# CROSS.net
KiCad netlist of a schematic drawn in EAGLE
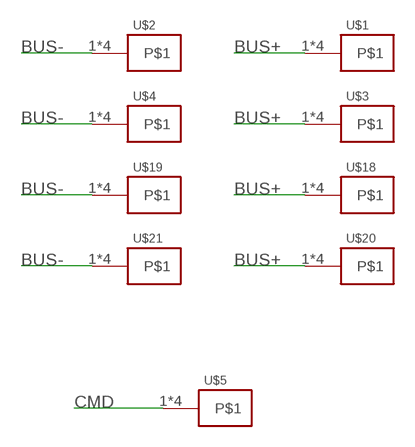
[diagram p0: schematic, sheet 1]

(export (version "E")
  (design (tool "Eeschema 10.0.6"))
  (components
    (comp (ref "U$1")
      (value "KCONNECT-")
      (footprint "eagle-import:KCONNECT-")
      (libsource (lib "eagle-import") (part "KCONNECT-"))
    )
    (comp (ref "U$2")
      (value "KCONNECT-")
      (footprint "eagle-import:KCONNECT-")
      (libsource (lib "eagle-import") (part "KCONNECT-"))
    )
    (comp (ref "U$3")
      (value "KCONNECT-")
      (footprint "eagle-import:KCONNECT-")
      (libsource (lib "eagle-import") (part "KCONNECT-"))
    )
    (comp (ref "U$4")
      (value "KCONNECT-")
      (footprint "eagle-import:KCONNECT-")
      (libsource (lib "eagle-import") (part "KCONNECT-"))
    )
    (comp (ref "U$5")
      (value "KCONNECTQUAD-")
      (footprint "eagle-import:KCONNECT-_QUAD")
      (libsource (lib "eagle-import") (part "KCONNECTQUAD-"))
    )
    (comp (ref "U$18")
      (value "KCONNECT-")
      (footprint "eagle-import:KCONNECT-")
      (libsource (lib "eagle-import") (part "KCONNECT-"))
    )
    (comp (ref "U$19")
      (value "KCONNECT-")
      (footprint "eagle-import:KCONNECT-")
      (libsource (lib "eagle-import") (part "KCONNECT-"))
    )
    (comp (ref "U$20")
      (value "KCONNECT-")
      (footprint "eagle-import:KCONNECT-")
      (libsource (lib "eagle-import") (part "KCONNECT-"))
    )
    (comp (ref "U$21")
      (value "KCONNECT-")
      (footprint "eagle-import:KCONNECT-")
      (libsource (lib "eagle-import") (part "KCONNECT-"))
    )
  )
  (nets
    (net (code "1") (name "/BUS+") (class "Default")
      (node (ref "U$1") (pin "1") (pinfunction "P$1_1") (pintype "bidirectional"))
      (node (ref "U$1") (pin "2") (pinfunction "P$1_2") (pintype "bidirectional"))
      (node (ref "U$1") (pin "3") (pinfunction "P$1_3") (pintype "bidirectional"))
      (node (ref "U$1") (pin "4") (pinfunction "P$1_4") (pintype "bidirectional"))
      (node (ref "U$18") (pin "1") (pinfunction "P$1_1") (pintype "bidirectional"))
      (node (ref "U$18") (pin "2") (pinfunction "P$1_2") (pintype "bidirectional"))
      (node (ref "U$18") (pin "3") (pinfunction "P$1_3") (pintype "bidirectional"))
      (node (ref "U$18") (pin "4") (pinfunction "P$1_4") (pintype "bidirectional"))
      (node (ref "U$20") (pin "1") (pinfunction "P$1_1") (pintype "bidirectional"))
      (node (ref "U$20") (pin "2") (pinfunction "P$1_2") (pintype "bidirectional"))
      (node (ref "U$20") (pin "3") (pinfunction "P$1_3") (pintype "bidirectional"))
      (node (ref "U$20") (pin "4") (pinfunction "P$1_4") (pintype "bidirectional"))
      (node (ref "U$3") (pin "1") (pinfunction "P$1_1") (pintype "bidirectional"))
      (node (ref "U$3") (pin "2") (pinfunction "P$1_2") (pintype "bidirectional"))
      (node (ref "U$3") (pin "3") (pinfunction "P$1_3") (pintype "bidirectional"))
      (node (ref "U$3") (pin "4") (pinfunction "P$1_4") (pintype "bidirectional"))
    )
    (net (code "2") (name "/BUS-") (class "Default")
      (node (ref "U$19") (pin "1") (pinfunction "P$1_1") (pintype "bidirectional"))
      (node (ref "U$19") (pin "2") (pinfunction "P$1_2") (pintype "bidirectional"))
      (node (ref "U$19") (pin "3") (pinfunction "P$1_3") (pintype "bidirectional"))
      (node (ref "U$19") (pin "4") (pinfunction "P$1_4") (pintype "bidirectional"))
      (node (ref "U$2") (pin "1") (pinfunction "P$1_1") (pintype "bidirectional"))
      (node (ref "U$2") (pin "2") (pinfunction "P$1_2") (pintype "bidirectional"))
      (node (ref "U$2") (pin "3") (pinfunction "P$1_3") (pintype "bidirectional"))
      (node (ref "U$2") (pin "4") (pinfunction "P$1_4") (pintype "bidirectional"))
      (node (ref "U$21") (pin "1") (pinfunction "P$1_1") (pintype "bidirectional"))
      (node (ref "U$21") (pin "2") (pinfunction "P$1_2") (pintype "bidirectional"))
      (node (ref "U$21") (pin "3") (pinfunction "P$1_3") (pintype "bidirectional"))
      (node (ref "U$21") (pin "4") (pinfunction "P$1_4") (pintype "bidirectional"))
      (node (ref "U$4") (pin "1") (pinfunction "P$1_1") (pintype "bidirectional"))
      (node (ref "U$4") (pin "2") (pinfunction "P$1_2") (pintype "bidirectional"))
      (node (ref "U$4") (pin "3") (pinfunction "P$1_3") (pintype "bidirectional"))
      (node (ref "U$4") (pin "4") (pinfunction "P$1_4") (pintype "bidirectional"))
    )
    (net (code "3") (name "/CMD") (class "Default")
      (node (ref "U$5") (pin "1") (pinfunction "P$1_1") (pintype "bidirectional"))
      (node (ref "U$5") (pin "2") (pinfunction "P$1_2") (pintype "bidirectional"))
      (node (ref "U$5") (pin "3") (pinfunction "P$1_3") (pintype "bidirectional"))
      (node (ref "U$5") (pin "4") (pinfunction "P$1_4") (pintype "bidirectional"))
    )
  )
)
